# qo-100-pa-20W.net
KiCad netlist of a schematic drawn in EAGLE
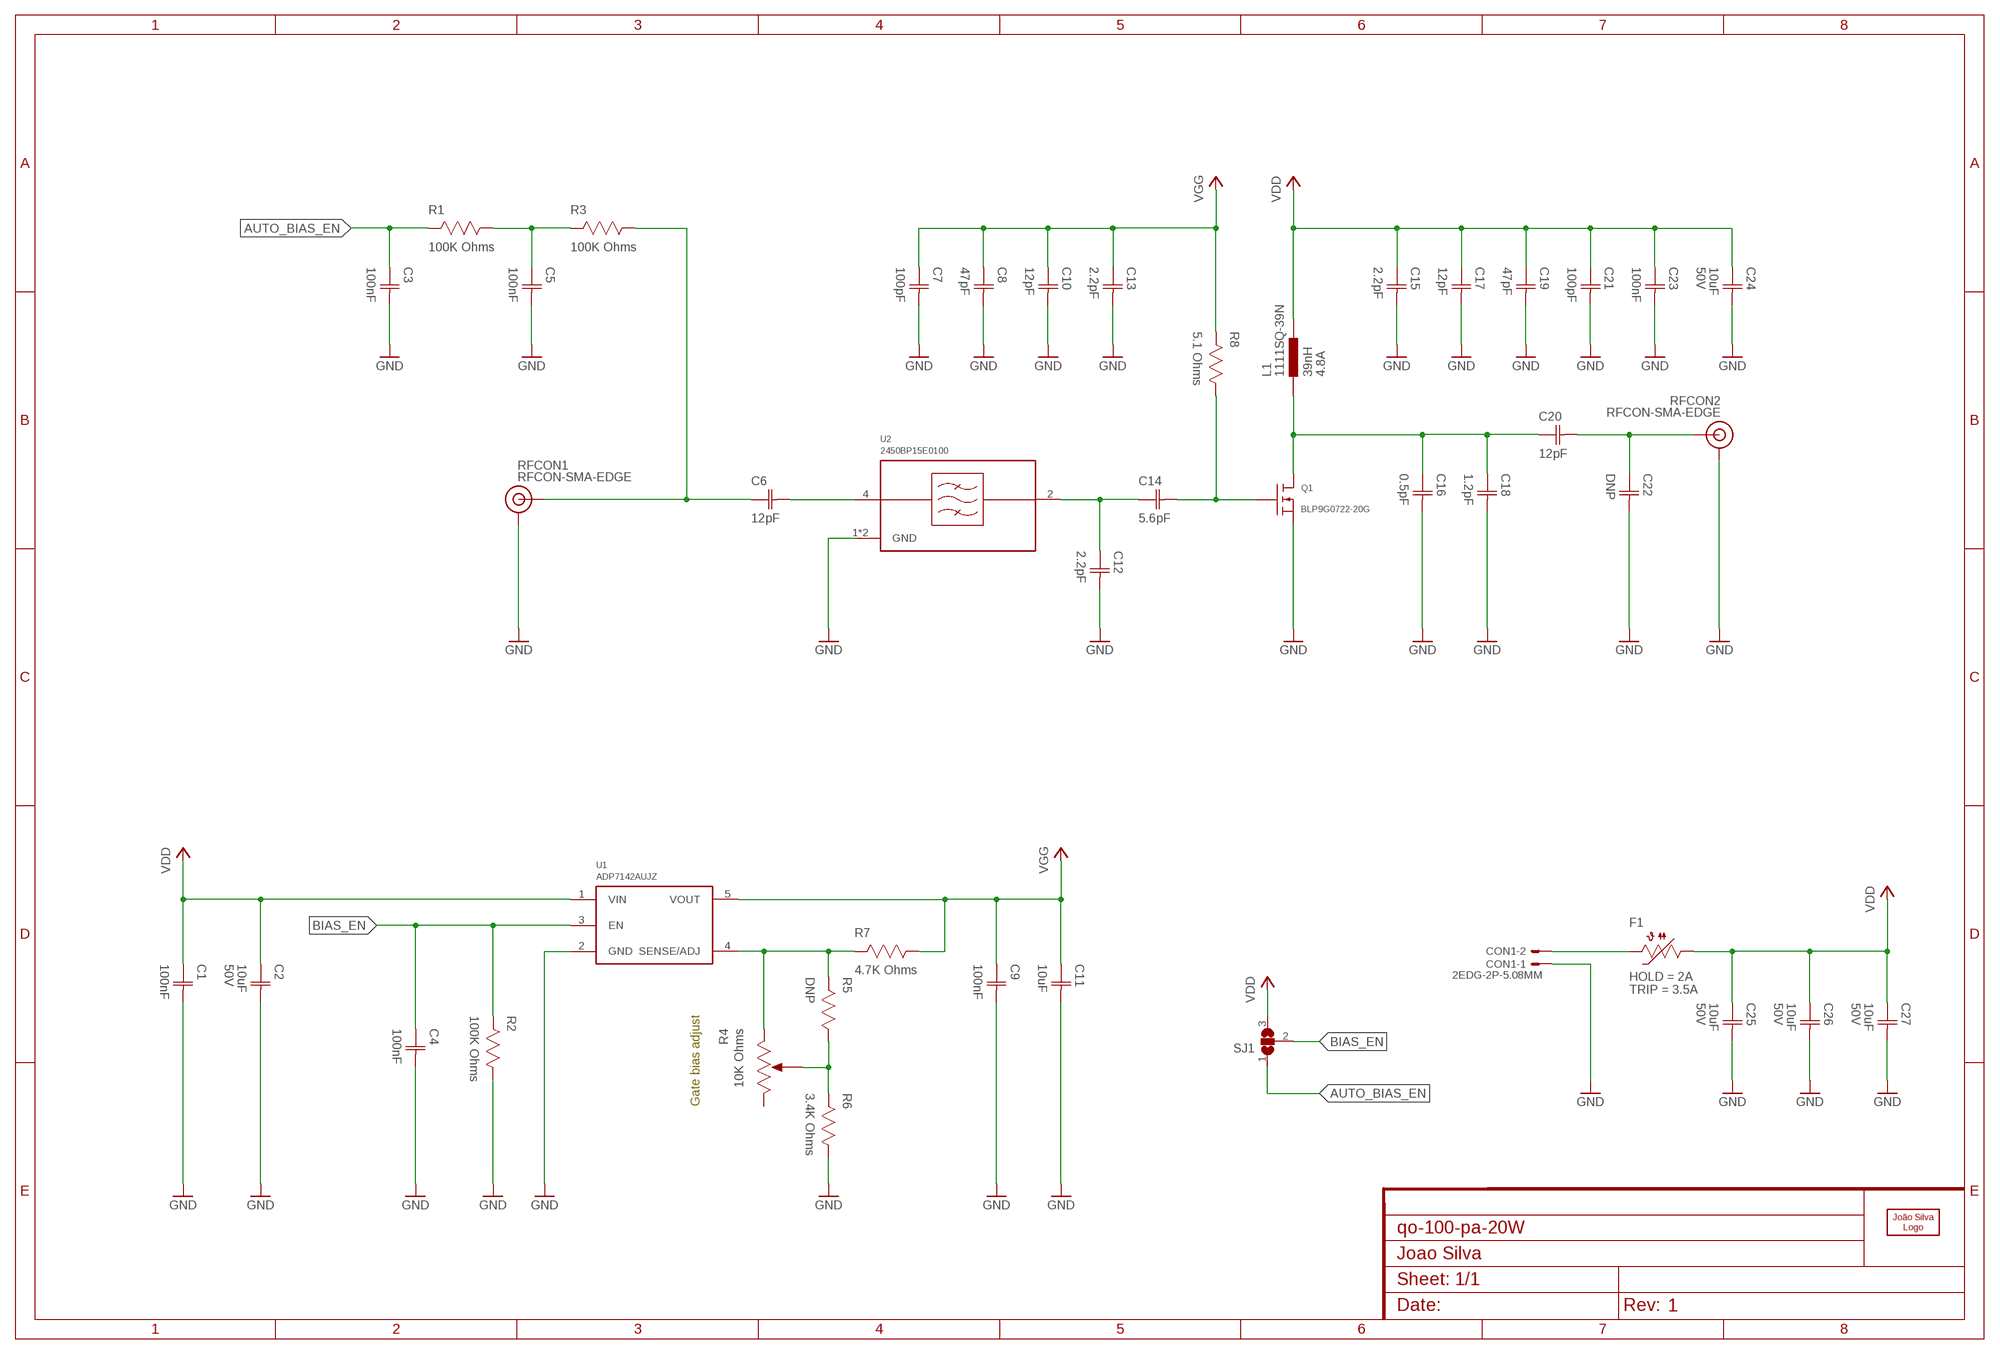
[diagram p0: schematic, sheet 1]

(export (version "E")
  (design (tool "Eeschema 10.0.6"))
  (components
    (comp (ref "C1")
      (value "100nF")
      (footprint "eagle-import:CAP0603")
      (libsource (lib "eagle-import") (part "CAPACITOR-0603"))
    )
    (comp (ref "C2")
      (value "10uF")
      (footprint "eagle-import:CAP1206")
      (fields (field (name "VOLTAGE") "50V"))
      (libsource (lib "eagle-import") (part "CAPACITOR-1206"))
    )
    (comp (ref "C3")
      (value "100nF")
      (footprint "eagle-import:CAP0603")
      (libsource (lib "eagle-import") (part "CAPACITOR-0603"))
    )
    (comp (ref "C4")
      (value "100nF")
      (footprint "eagle-import:CAP0603")
      (libsource (lib "eagle-import") (part "CAPACITOR-0603"))
    )
    (comp (ref "C5")
      (value "100nF")
      (footprint "eagle-import:CAP0603")
      (libsource (lib "eagle-import") (part "CAPACITOR-0603"))
    )
    (comp (ref "C6")
      (value "12pF")
      (footprint "eagle-import:CAP0603")
      (libsource (lib "eagle-import") (part "CAPACITOR-0603"))
    )
    (comp (ref "C7")
      (value "100pF")
      (footprint "eagle-import:CAP0603")
      (libsource (lib "eagle-import") (part "CAPACITOR-0603"))
    )
    (comp (ref "C8")
      (value "47pF")
      (footprint "eagle-import:CAP0603")
      (libsource (lib "eagle-import") (part "CAPACITOR-0603"))
    )
    (comp (ref "C9")
      (value "100nF")
      (footprint "eagle-import:CAP0603")
      (libsource (lib "eagle-import") (part "CAPACITOR-0603"))
    )
    (comp (ref "C10")
      (value "12pF")
      (footprint "eagle-import:CAP0603")
      (libsource (lib "eagle-import") (part "CAPACITOR-0603"))
    )
    (comp (ref "C11")
      (value "10uF")
      (footprint "eagle-import:CAP0603")
      (libsource (lib "eagle-import") (part "CAPACITOR-0603"))
    )
    (comp (ref "C12")
      (value "2.2pF")
      (footprint "eagle-import:CAP0603")
      (libsource (lib "eagle-import") (part "CAPACITOR-0603"))
    )
    (comp (ref "C13")
      (value "2.2pF")
      (footprint "eagle-import:CAP0603")
      (libsource (lib "eagle-import") (part "CAPACITOR-0603"))
    )
    (comp (ref "C14")
      (value "5.6pF")
      (footprint "eagle-import:CAP0603")
      (libsource (lib "eagle-import") (part "CAPACITOR-0603"))
    )
    (comp (ref "C15")
      (value "2.2pF")
      (footprint "eagle-import:CAP0603")
      (libsource (lib "eagle-import") (part "CAPACITOR-0603"))
    )
    (comp (ref "C16")
      (value "0.5pF")
      (footprint "eagle-import:CAP0603")
      (libsource (lib "eagle-import") (part "CAPACITOR-0603"))
    )
    (comp (ref "C17")
      (value "12pF")
      (footprint "eagle-import:CAP0603")
      (libsource (lib "eagle-import") (part "CAPACITOR-0603"))
    )
    (comp (ref "C18")
      (value "1.2pF")
      (footprint "eagle-import:CAP0603")
      (libsource (lib "eagle-import") (part "CAPACITOR-0603"))
    )
    (comp (ref "C19")
      (value "47pF")
      (footprint "eagle-import:CAP0603")
      (libsource (lib "eagle-import") (part "CAPACITOR-0603"))
    )
    (comp (ref "C20")
      (value "12pF")
      (footprint "eagle-import:CAP0603")
      (libsource (lib "eagle-import") (part "CAPACITOR-0603"))
    )
    (comp (ref "C21")
      (value "100pF")
      (footprint "eagle-import:CAP0603")
      (libsource (lib "eagle-import") (part "CAPACITOR-0603"))
    )
    (comp (ref "C22")
      (value "DNP")
      (footprint "eagle-import:CAP0603")
      (libsource (lib "eagle-import") (part "CAPACITOR-0603"))
    )
    (comp (ref "C23")
      (value "100nF")
      (footprint "eagle-import:CAP0603")
      (libsource (lib "eagle-import") (part "CAPACITOR-0603"))
    )
    (comp (ref "C24")
      (value "10uF")
      (footprint "eagle-import:CAP1206")
      (fields (field (name "VOLTAGE") "50V"))
      (libsource (lib "eagle-import") (part "CAPACITOR-1206"))
    )
    (comp (ref "C25")
      (value "10uF")
      (footprint "eagle-import:CAP1206")
      (fields (field (name "VOLTAGE") "50V"))
      (libsource (lib "eagle-import") (part "CAPACITOR-1206"))
    )
    (comp (ref "C26")
      (value "10uF")
      (footprint "eagle-import:CAP1206")
      (fields (field (name "VOLTAGE") "50V"))
      (libsource (lib "eagle-import") (part "CAPACITOR-1206"))
    )
    (comp (ref "C27")
      (value "10uF")
      (footprint "eagle-import:CAP1206")
      (fields (field (name "VOLTAGE") "50V"))
      (libsource (lib "eagle-import") (part "CAPACITOR-1206"))
    )
    (comp (ref "CON1")
      (value "2EDG-2P-5.08MM")
      (footprint "eagle-import:2EDG-2P-5.08MM")
      (libsource (lib "eagle-import") (part "2EDG-2P-5.08MM"))
    )
    (comp (ref "F1")
      (value "PTC1206")
      (footprint "eagle-import:1206")
      (fields (field (name "HOLD") "2A") (field (name "TRIP") "3.5A"))
      (libsource (lib "eagle-import") (part "PTC1206"))
    )
    (comp (ref "L1")
      (value "39nH")
      (footprint "eagle-import:1111SQ")
      (fields (field (name "CURRENT") "4.8A") (field (name "REF") "1111SQ-39N"))
      (libsource (lib "eagle-import") (part "1111SQ-39N"))
    )
    (comp (ref "LOGO1")
      (value "JS-10MM")
      (footprint "eagle-import:JS_10MM")
      (libsource (lib "eagle-import") (part "JS-10MM"))
    )
    (comp (ref "Q1")
      (value "BLP9G0722-20G")
      (footprint "eagle-import:SOT1483-1")
      (libsource (lib "eagle-import") (part "BLP9G0722-20G"))
    )
    (comp (ref "R1")
      (value "100K Ohms")
      (footprint "eagle-import:RES0603")
      (libsource (lib "eagle-import") (part "RESISTOR-0603"))
    )
    (comp (ref "R2")
      (value "100K Ohms")
      (footprint "eagle-import:RES0603")
      (libsource (lib "eagle-import") (part "RESISTOR-0603"))
    )
    (comp (ref "R3")
      (value "100K Ohms")
      (footprint "eagle-import:RES0603")
      (libsource (lib "eagle-import") (part "RESISTOR-0603"))
    )
    (comp (ref "R4")
      (value "10K Ohms")
      (footprint "eagle-import:POT3MM")
      (libsource (lib "eagle-import") (part "POTENTIOMETER-SMD-3X3"))
    )
    (comp (ref "R5")
      (value "DNP")
      (footprint "eagle-import:RES0603")
      (libsource (lib "eagle-import") (part "RESISTOR-0603"))
    )
    (comp (ref "R6")
      (value "3.4K Ohms")
      (footprint "eagle-import:RES0603")
      (libsource (lib "eagle-import") (part "RESISTOR-0603"))
    )
    (comp (ref "R7")
      (value "4.7K Ohms")
      (footprint "eagle-import:RES0603")
      (libsource (lib "eagle-import") (part "RESISTOR-0603"))
    )
    (comp (ref "R8")
      (value "5.1 Ohms")
      (footprint "eagle-import:RES0603")
      (libsource (lib "eagle-import") (part "RESISTOR-0603"))
    )
    (comp (ref "RFCON1")
      (value "RFCON-SMA-EDGE")
      (footprint "eagle-import:SMA-EDGE")
      (libsource (lib "eagle-import") (part "RFCON-SMA-EDGE"))
    )
    (comp (ref "RFCON2")
      (value "RFCON-SMA-EDGE")
      (footprint "eagle-import:SMA-EDGE")
      (libsource (lib "eagle-import") (part "RFCON-SMA-EDGE"))
    )
    (comp (ref "SJ1")
      (value "SJ2S")
      (footprint "eagle-import:SJ2_S")
      (libsource (lib "eagle-import") (part "SJ2S"))
    )
    (comp (ref "U1")
      (value "ADP7142AUJZ")
      (footprint "eagle-import:SOT23-5")
      (libsource (lib "eagle-import") (part "ADP7142AUJZ"))
    )
    (comp (ref "U2")
      (value "2450BP15E0100")
      (footprint "eagle-import:2450BP15E0100")
      (libsource (lib "eagle-import") (part "2450BP15E0100"))
    )
  )
  (nets
    (net (code "1") (name "AUTO_BIAS_EN") (class "Default")
      (node (ref "C3") (pin "1") (pinfunction "C1_1") (pintype "passive"))
      (node (ref "R1") (pin "2") (pinfunction "2_2") (pintype "passive"))
      (node (ref "SJ1") (pin "1") (pinfunction "1_1") (pintype "passive"))
    )
    (net (code "2") (name "BIAS_EN") (class "Default")
      (node (ref "C4") (pin "1") (pinfunction "C1_1") (pintype "passive"))
      (node (ref "R2") (pin "2") (pinfunction "2_2") (pintype "passive"))
      (node (ref "SJ1") (pin "2") (pinfunction "2_2") (pintype "passive"))
      (node (ref "U1") (pin "3") (pinfunction "EN_3") (pintype "bidirectional"))
    )
    (net (code "3") (name "GND") (class "Default")
      (node (ref "C1") (pin "2") (pinfunction "C2_2") (pintype "passive"))
      (node (ref "C10") (pin "2") (pinfunction "C2_2") (pintype "passive"))
      (node (ref "C11") (pin "2") (pinfunction "C2_2") (pintype "passive"))
      (node (ref "C12") (pin "2") (pinfunction "C2_2") (pintype "passive"))
      (node (ref "C13") (pin "2") (pinfunction "C2_2") (pintype "passive"))
      (node (ref "C15") (pin "2") (pinfunction "C2_2") (pintype "passive"))
      (node (ref "C16") (pin "2") (pinfunction "C2_2") (pintype "passive"))
      (node (ref "C17") (pin "2") (pinfunction "C2_2") (pintype "passive"))
      (node (ref "C18") (pin "2") (pinfunction "C2_2") (pintype "passive"))
      (node (ref "C19") (pin "2") (pinfunction "C2_2") (pintype "passive"))
      (node (ref "C2") (pin "2") (pinfunction "C2_2") (pintype "passive"))
      (node (ref "C21") (pin "2") (pinfunction "C2_2") (pintype "passive"))
      (node (ref "C22") (pin "2") (pinfunction "C2_2") (pintype "passive"))
      (node (ref "C23") (pin "2") (pinfunction "C2_2") (pintype "passive"))
      (node (ref "C24") (pin "2") (pinfunction "C2_2") (pintype "passive"))
      (node (ref "C25") (pin "2") (pinfunction "C2_2") (pintype "passive"))
      (node (ref "C26") (pin "2") (pinfunction "C2_2") (pintype "passive"))
      (node (ref "C27") (pin "2") (pinfunction "C2_2") (pintype "passive"))
      (node (ref "C3") (pin "2") (pinfunction "C2_2") (pintype "passive"))
      (node (ref "C4") (pin "2") (pinfunction "C2_2") (pintype "passive"))
      (node (ref "C5") (pin "2") (pinfunction "C2_2") (pintype "passive"))
      (node (ref "C7") (pin "2") (pinfunction "C2_2") (pintype "passive"))
      (node (ref "C8") (pin "2") (pinfunction "C2_2") (pintype "passive"))
      (node (ref "C9") (pin "2") (pinfunction "C2_2") (pintype "passive"))
      (node (ref "CON1") (pin "P$1") (pinfunction "S_P$1") (pintype "passive"))
      (node (ref "Q1") (pin "3@0") (pinfunction "S_3@0") (pintype "passive"))
      (node (ref "Q1") (pin "3@1") (pinfunction "S_3@1") (pintype "passive"))
      (node (ref "Q1") (pin "3@2") (pinfunction "S_3@2") (pintype "passive"))
      (node (ref "R2") (pin "1") (pinfunction "1_1") (pintype "passive"))
      (node (ref "R6") (pin "1") (pinfunction "1_1") (pintype "passive"))
      (node (ref "RFCON1") (pin "GND@0") (pinfunction "GND_GND@0") (pintype "bidirectional"))
      (node (ref "RFCON1") (pin "GND@1") (pinfunction "GND_GND@1") (pintype "bidirectional"))
      (node (ref "RFCON1") (pin "GND@2") (pinfunction "GND_GND@2") (pintype "bidirectional"))
      (node (ref "RFCON1") (pin "GND@3") (pinfunction "GND_GND@3") (pintype "bidirectional"))
      (node (ref "RFCON2") (pin "GND@0") (pinfunction "GND_GND@0") (pintype "bidirectional"))
      (node (ref "RFCON2") (pin "GND@1") (pinfunction "GND_GND@1") (pintype "bidirectional"))
      (node (ref "RFCON2") (pin "GND@2") (pinfunction "GND_GND@2") (pintype "bidirectional"))
      (node (ref "RFCON2") (pin "GND@3") (pinfunction "GND_GND@3") (pintype "bidirectional"))
      (node (ref "U1") (pin "2") (pinfunction "GND_2") (pintype "bidirectional"))
      (node (ref "U2") (pin "1") (pinfunction "GND_1") (pintype "bidirectional"))
      (node (ref "U2") (pin "3") (pinfunction "GND_3") (pintype "bidirectional"))
    )
    (net (code "4") (name "Net-(C5-C1)") (class "Default")
      (node (ref "C5") (pin "1") (pinfunction "C1_1") (pintype "passive"))
      (node (ref "R1") (pin "1") (pinfunction "1_1") (pintype "passive"))
      (node (ref "R3") (pin "2") (pinfunction "2_2") (pintype "passive"))
    )
    (net (code "5") (name "Net-(C6-C1)") (class "Default")
      (node (ref "C6") (pin "1") (pinfunction "C1_1") (pintype "passive"))
      (node (ref "R3") (pin "1") (pinfunction "1_1") (pintype "passive"))
      (node (ref "RFCON1") (pin "SIG") (pinfunction "SIGNAL_SIG") (pintype "bidirectional"))
    )
    (net (code "6") (name "Net-(C6-C2)") (class "Default")
      (node (ref "C6") (pin "2") (pinfunction "C2_2") (pintype "passive"))
      (node (ref "U2") (pin "4") (pinfunction "RFIN_4") (pintype "bidirectional"))
    )
    (net (code "7") (name "Net-(C12-C1)") (class "Default")
      (node (ref "C12") (pin "1") (pinfunction "C1_1") (pintype "passive"))
      (node (ref "C14") (pin "1") (pinfunction "C1_1") (pintype "passive"))
      (node (ref "U2") (pin "2") (pinfunction "RFOUT_2") (pintype "bidirectional"))
    )
    (net (code "8") (name "Net-(C14-C2)") (class "Default")
      (node (ref "C14") (pin "2") (pinfunction "C2_2") (pintype "passive"))
      (node (ref "Q1") (pin "2") (pinfunction "G_2") (pintype "passive"))
      (node (ref "R8") (pin "1") (pinfunction "1_1") (pintype "passive"))
    )
    (net (code "9") (name "Net-(C16-C1)") (class "Default")
      (node (ref "C16") (pin "1") (pinfunction "C1_1") (pintype "passive"))
      (node (ref "C18") (pin "1") (pinfunction "C1_1") (pintype "passive"))
      (node (ref "C20") (pin "1") (pinfunction "C1_1") (pintype "passive"))
      (node (ref "L1") (pin "1") (pinfunction "1_1") (pintype "passive"))
      (node (ref "Q1") (pin "1") (pinfunction "D_1") (pintype "passive"))
    )
    (net (code "10") (name "Net-(C20-C2)") (class "Default")
      (node (ref "C20") (pin "2") (pinfunction "C2_2") (pintype "passive"))
      (node (ref "C22") (pin "1") (pinfunction "C1_1") (pintype "passive"))
      (node (ref "RFCON2") (pin "SIG") (pinfunction "SIGNAL_SIG") (pintype "bidirectional"))
    )
    (net (code "11") (name "Net-(CON1B-S)") (class "Default")
      (node (ref "CON1") (pin "P$2") (pinfunction "S_P$2") (pintype "passive"))
      (node (ref "F1") (pin "2") (pinfunction "2_2") (pintype "passive"))
    )
    (net (code "12") (name "Net-(R4-CCW)") (class "Default")
      (node (ref "R4") (pin "1") (pinfunction "CCW_1") (pintype "passive"))
      (node (ref "R5") (pin "2") (pinfunction "2_2") (pintype "passive"))
      (node (ref "R7") (pin "2") (pinfunction "2_2") (pintype "passive"))
      (node (ref "U1") (pin "4") (pinfunction "SENSE/ADJ_4") (pintype "bidirectional"))
    )
    (net (code "13") (name "Net-(R4-WIPER)") (class "Default")
      (node (ref "R4") (pin "2") (pinfunction "WIPER_2") (pintype "passive"))
      (node (ref "R5") (pin "1") (pinfunction "1_1") (pintype "passive"))
      (node (ref "R6") (pin "2") (pinfunction "2_2") (pintype "passive"))
    )
    (net (code "14") (name "VDD") (class "Default")
      (node (ref "C1") (pin "1") (pinfunction "C1_1") (pintype "passive"))
      (node (ref "C15") (pin "1") (pinfunction "C1_1") (pintype "passive"))
      (node (ref "C17") (pin "1") (pinfunction "C1_1") (pintype "passive"))
      (node (ref "C19") (pin "1") (pinfunction "C1_1") (pintype "passive"))
      (node (ref "C2") (pin "1") (pinfunction "C1_1") (pintype "passive"))
      (node (ref "C21") (pin "1") (pinfunction "C1_1") (pintype "passive"))
      (node (ref "C23") (pin "1") (pinfunction "C1_1") (pintype "passive"))
      (node (ref "C24") (pin "1") (pinfunction "C1_1") (pintype "passive"))
      (node (ref "C25") (pin "1") (pinfunction "C1_1") (pintype "passive"))
      (node (ref "C26") (pin "1") (pinfunction "C1_1") (pintype "passive"))
      (node (ref "C27") (pin "1") (pinfunction "C1_1") (pintype "passive"))
      (node (ref "F1") (pin "1") (pinfunction "1_1") (pintype "passive"))
      (node (ref "L1") (pin "2") (pinfunction "2_2") (pintype "passive"))
      (node (ref "SJ1") (pin "3") (pinfunction "3_3") (pintype "passive"))
      (node (ref "U1") (pin "1") (pinfunction "VIN_1") (pintype "bidirectional"))
    )
    (net (code "15") (name "VGG") (class "Default")
      (node (ref "C10") (pin "1") (pinfunction "C1_1") (pintype "passive"))
      (node (ref "C11") (pin "1") (pinfunction "C1_1") (pintype "passive"))
      (node (ref "C13") (pin "1") (pinfunction "C1_1") (pintype "passive"))
      (node (ref "C7") (pin "1") (pinfunction "C1_1") (pintype "passive"))
      (node (ref "C8") (pin "1") (pinfunction "C1_1") (pintype "passive"))
      (node (ref "C9") (pin "1") (pinfunction "C1_1") (pintype "passive"))
      (node (ref "R7") (pin "1") (pinfunction "1_1") (pintype "passive"))
      (node (ref "R8") (pin "2") (pinfunction "2_2") (pintype "passive"))
      (node (ref "U1") (pin "5") (pinfunction "VOUT_5") (pintype "bidirectional"))
    )
    (net (code "16") (name "unconnected-(R4-CW-Pad3)") (class "Default")
      (node (ref "R4") (pin "3") (pinfunction "CW_3") (pintype "passive"))
    )
  )
)
